# Hi_Current.net
KiCad netlist of a schematic drawn in Altium Designer
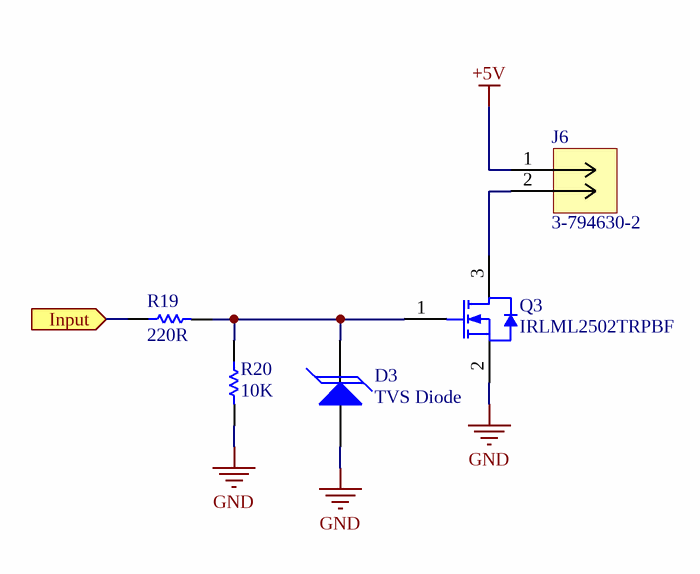
[diagram p0: Hi_Current.SchDoc]

(export (version "E")
  (design (tool "Eeschema 10.0.6"))
  (components
    (comp (ref "D3")
      (value "TVS Diode")
      (footprint "SOD-123")
      (description "PTVS3V3S1UR,115\r\nDigikey part no. 1727-5228-1-ND")
      (libsource (lib "Moonlight-Components") (part "TVS Diode"))
    )
    (comp (ref "J6")
      (value "3-794630-2")
      (footprint "3-794630-2")
      (description "Digikey part no. A33219-ND")
      (fields (field (name "COPYRIGHT") "Copyright (C) 2018 Accelerated Designs. All rights reserved"))
      (libsource (lib "Moonlight-Components") (part "2 pin vertical molex"))
    )
    (comp (ref "Q3")
      (value "IRLML2502TRPBF")
      (footprint "INTR-SOT-23-3_V")
      (description "N-Channel HEXFET(R) Power MOSFET, 20 V VDS, +/- 12 V VGS, 4.2 A, 3-Pin SOT23, RoHS, Tape and Reel")
      (fields (field (name "MANUFACTURER") "International Rectifier"))
      (libsource (lib "Moonlight-Components") (part "IRLML2502TRPBF"))
    )
    (comp (ref "R19")
      (value "220R")
      (footprint "0603_RES")
      (libsource (lib "Moonlight-Components") (part "Resistor"))
    )
    (comp (ref "R20")
      (value "10K")
      (footprint "0603_RES")
      (libsource (lib "Moonlight-Components") (part "Resistor"))
    )
  )
  (nets
    (net (code "1") (name "+5V") (class "Default")
      (node (ref "J6") (pin "1") (pinfunction "1_1") (pintype "passive"))
    )
    (net (code "2") (name "/Input") (class "Default")
      (node (ref "R19") (pin "1") (pinfunction "1_1") (pintype "passive"))
    )
    (net (code "3") (name "GND") (class "Default")
      (node (ref "D3") (pin "2") (pinfunction "A_2") (pintype "passive"))
      (node (ref "Q3") (pin "2") (pinfunction "S_2") (pintype "passive"))
      (node (ref "R20") (pin "2") (pinfunction "2_2") (pintype "passive"))
    )
    (net (code "4") (name "Net-(D3-K)") (class "Default")
      (node (ref "D3") (pin "1") (pinfunction "K_1") (pintype "passive"))
      (node (ref "Q3") (pin "1") (pinfunction "G_1") (pintype "passive"))
      (node (ref "R19") (pin "2") (pinfunction "2_2") (pintype "passive"))
      (node (ref "R20") (pin "1") (pinfunction "1_1") (pintype "passive"))
    )
    (net (code "5") (name "Net-(Q3-D)") (class "Default")
      (node (ref "J6") (pin "2") (pinfunction "2_2") (pintype "passive"))
      (node (ref "Q3") (pin "3") (pinfunction "D_3") (pintype "passive"))
    )
  )
)
